# MCU-STM32F767.net
KiCad netlist of a schematic drawn in Altium Designer
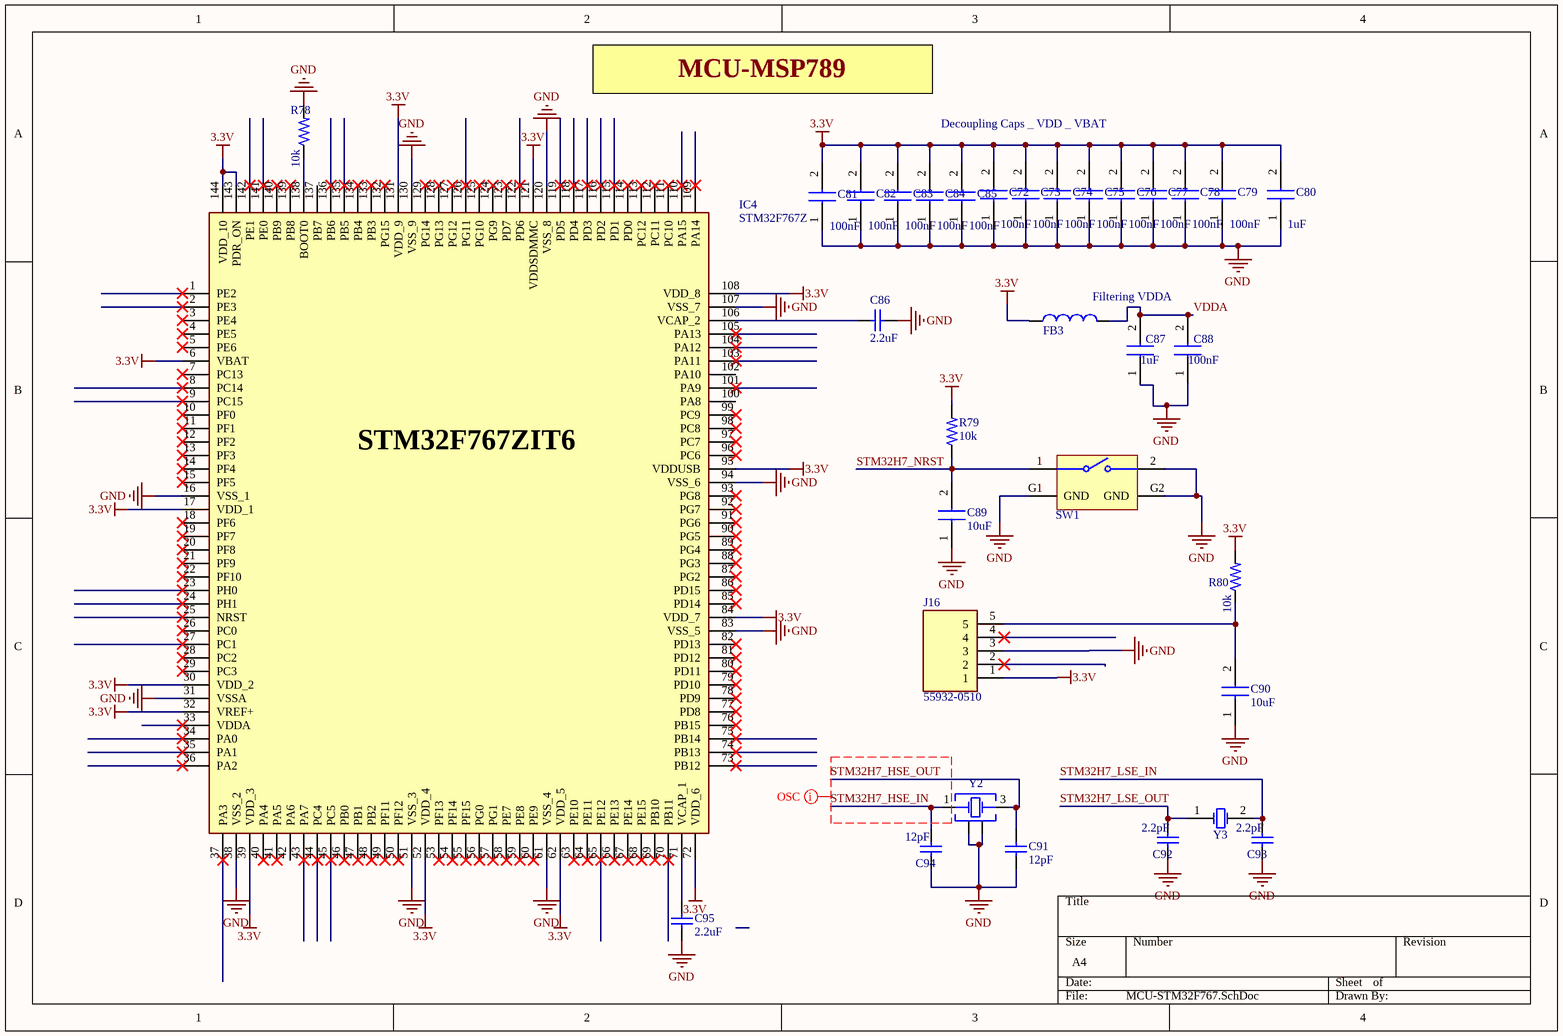
[diagram p0: MCU-STM32F767.SchDoc]

(export (version "E")
  (design (tool "Eeschema 10.0.6"))
  (components
    (comp (ref "C72")
      (value "100nF")
      (footprint "CAPC1005X55N")
      (description "Capacitor")
      (fields
        (field (name "MANUFACTURER_PART_NUMBER") "CL05B104KO5NNNC")
        (field (name "MOUSER PART NUMBER") "187-CL05B104KO5NNNC")
      )
      (libsource (lib "lib-hiony") (part "6V 100nF X7R ±10% 0402 Multilayer"))
    )
    (comp (ref "C73")
      (value "100nF")
      (footprint "CAPC1005X55N")
      (description "Capacitor")
      (fields
        (field (name "MANUFACTURER_PART_NUMBER") "CL05B104KO5NNNC")
        (field (name "MOUSER PART NUMBER") "187-CL05B104KO5NNNC")
      )
      (libsource (lib "lib-hiony") (part "6V 100nF X7R ±10% 0402 Multilayer"))
    )
    (comp (ref "C74")
      (value "100nF")
      (footprint "CAPC1005X55N")
      (description "Capacitor")
      (fields
        (field (name "MANUFACTURER_PART_NUMBER") "CL05B104KO5NNNC")
        (field (name "MOUSER PART NUMBER") "187-CL05B104KO5NNNC")
      )
      (libsource (lib "lib-hiony") (part "6V 100nF X7R ±10% 0402 Multilayer"))
    )
    (comp (ref "C75")
      (value "100nF")
      (footprint "CAPC1005X55N")
      (description "Capacitor")
      (fields
        (field (name "MANUFACTURER_PART_NUMBER") "CL05B104KO5NNNC")
        (field (name "MOUSER PART NUMBER") "187-CL05B104KO5NNNC")
      )
      (libsource (lib "lib-hiony") (part "6V 100nF X7R ±10% 0402 Multilayer"))
    )
    (comp (ref "C76")
      (value "100nF")
      (footprint "CAPC1005X55N")
      (description "Capacitor")
      (fields
        (field (name "MANUFACTURER_PART_NUMBER") "CL05B104KO5NNNC")
        (field (name "MOUSER PART NUMBER") "187-CL05B104KO5NNNC")
      )
      (libsource (lib "lib-hiony") (part "6V 100nF X7R ±10% 0402 Multilayer"))
    )
    (comp (ref "C77")
      (value "100nF")
      (footprint "CAPC1005X55N")
      (description "Capacitor")
      (fields
        (field (name "MANUFACTURER_PART_NUMBER") "CL05B104KO5NNNC")
        (field (name "MOUSER PART NUMBER") "187-CL05B104KO5NNNC")
      )
      (libsource (lib "lib-hiony") (part "6V 100nF X7R ±10% 0402 Multilayer"))
    )
    (comp (ref "C78")
      (value "100nF")
      (footprint "CAPC1005X55N")
      (description "Capacitor")
      (fields
        (field (name "MANUFACTURER_PART_NUMBER") "CL05B104KO5NNNC")
        (field (name "MOUSER PART NUMBER") "187-CL05B104KO5NNNC")
      )
      (libsource (lib "lib-hiony") (part "6V 100nF X7R ±10% 0402 Multilayer"))
    )
    (comp (ref "C79")
      (value "100nF")
      (footprint "CAPC1005X55N")
      (description "Capacitor")
      (fields
        (field (name "MANUFACTURER_PART_NUMBER") "CL05B104KO5NNNC")
        (field (name "MOUSER PART NUMBER") "187-CL05B104KO5NNNC")
      )
      (libsource (lib "lib-hiony") (part "6V 100nF X7R ±10% 0402 Multilayer"))
    )
    (comp (ref "C80")
      (value "1uF")
      (footprint "CAPC1005X55N")
      (description "Capacitor")
      (fields
        (field (name "MANUFACTURER_PART_NUMBER") "CL05B104KO5NNNC")
        (field (name "MOUSER PART NUMBER") "187-CL05B104KO5NNNC")
      )
      (libsource (lib "lib-hiony") (part "6V 100nF X7R ±10% 0402 Multilayer"))
    )
    (comp (ref "C81")
      (value "100nF")
      (footprint "CAPC1005X55N")
      (description "Capacitor")
      (fields
        (field (name "MANUFACTURER_PART_NUMBER") "CL05B104KO5NNNC")
        (field (name "MOUSER PART NUMBER") "187-CL05B104KO5NNNC")
      )
      (libsource (lib "lib-hiony") (part "6V 100nF X7R ±10% 0402 Multilayer"))
    )
    (comp (ref "C82")
      (value "100nF")
      (footprint "CAPC1005X55N")
      (description "Capacitor")
      (fields
        (field (name "MANUFACTURER_PART_NUMBER") "CL05B104KO5NNNC")
        (field (name "MOUSER PART NUMBER") "187-CL05B104KO5NNNC")
      )
      (libsource (lib "lib-hiony") (part "6V 100nF X7R ±10% 0402 Multilayer"))
    )
    (comp (ref "C83")
      (value "100nF")
      (footprint "CAPC1005X55N")
      (description "Capacitor")
      (fields
        (field (name "MANUFACTURER_PART_NUMBER") "CL05B104KO5NNNC")
        (field (name "MOUSER PART NUMBER") "187-CL05B104KO5NNNC")
      )
      (libsource (lib "lib-hiony") (part "6V 100nF X7R ±10% 0402 Multilayer"))
    )
    (comp (ref "C84")
      (value "100nF")
      (footprint "CAPC1005X55N")
      (description "Capacitor")
      (fields
        (field (name "MANUFACTURER_PART_NUMBER") "CL05B104KO5NNNC")
        (field (name "MOUSER PART NUMBER") "187-CL05B104KO5NNNC")
      )
      (libsource (lib "lib-hiony") (part "6V 100nF X7R ±10% 0402 Multilayer"))
    )
    (comp (ref "C85")
      (value "100nF")
      (footprint "CAPC1005X55N")
      (description "Capacitor")
      (fields
        (field (name "MANUFACTURER_PART_NUMBER") "CL05B104KO5NNNC")
        (field (name "MOUSER PART NUMBER") "187-CL05B104KO5NNNC")
      )
      (libsource (lib "lib-hiony") (part "6V 100nF X7R ±10% 0402 Multilayer"))
    )
    (comp (ref "C86")
      (value "2.2uF")
      (footprint "WCAP-CSST_0603_L1.6W0.8H0.8_Reflow")
      (fields
        (field (name "MANUFACTURER PART NUMBER") "885382206001")
        (field (name "MANUFACTURER") "Wurth Elektronik")
      )
      (libsource (lib "Schlib1") (part "0.1uF capacitor"))
    )
    (comp (ref "C87")
      (value "1uF")
      (footprint "CAPC1005X55N")
      (description "Capacitor")
      (fields
        (field (name "MANUFACTURER_PART_NUMBER") "CL05B104KO5NNNC")
        (field (name "MOUSER PART NUMBER") "187-CL05B104KO5NNNC")
      )
      (libsource (lib "*") (part "CL05B104KO5NNNC"))
    )
    (comp (ref "C88")
      (value "100nF")
      (footprint "CAPC1005X55N")
      (description "Capacitor")
      (fields
        (field (name "MANUFACTURER_PART_NUMBER") "CL05B104KO5NNNC")
        (field (name "MOUSER PART NUMBER") "187-CL05B104KO5NNNC")
      )
      (libsource (lib "*") (part "CL05B104KO5NNNC"))
    )
    (comp (ref "C89")
      (value "10uF")
      (footprint "CAPC1005X55N")
      (description "Capacitor")
      (fields
        (field (name "MANUFACTURER_PART_NUMBER") "CC0603KRX7R9BB104")
        (field (name "MOUSER PART NUMBER") "603-CC603KRX7R9BB104")
      )
      (libsource (lib "Schlib1") (part "0.1uF_603_Capacitor_NL"))
    )
    (comp (ref "C90")
      (value "10uF")
      (footprint "CAPC1005X55N")
      (description "Capacitor")
      (fields
        (field (name "MANUFACTURER_PART_NUMBER") "CC0603KRX7R9BB104")
        (field (name "MOUSER PART NUMBER") "603-CC603KRX7R9BB104")
      )
      (libsource (lib "Schlib1") (part "0.1uF_603_Capacitor_NL"))
    )
    (comp (ref "C91")
      (value "12pF")
      (footprint "WCAP-CSST_0603_L1.6W0.8H0.8_Reflow")
      (fields
        (field (name "MANUFACTURER PART NUMBER") "885382206001")
        (field (name "MANUFACTURER") "Wurth Elektronik")
      )
      (libsource (lib "Schlib1") (part "0.1uF capacitor"))
    )
    (comp (ref "C92")
      (value "2.2pF")
      (footprint "WCAP-CSST_0603_L1.6W0.8H0.8_Reflow")
      (fields
        (field (name "MANUFACTURER PART NUMBER") "885382206001")
        (field (name "MANUFACTURER") "Wurth Elektronik")
      )
      (libsource (lib "Schlib1") (part "0.1uF capacitor"))
    )
    (comp (ref "C93")
      (value "2.2pF")
      (footprint "WCAP-CSST_0603_L1.6W0.8H0.8_Reflow")
      (fields
        (field (name "MANUFACTURER PART NUMBER") "885382206001")
        (field (name "MANUFACTURER") "Wurth Elektronik")
      )
      (libsource (lib "Schlib1") (part "0.1uF capacitor"))
    )
    (comp (ref "C94")
      (value "12pF")
      (footprint "WCAP-CSST_0603_L1.6W0.8H0.8_Reflow")
      (fields
        (field (name "MANUFACTURER PART NUMBER") "885382206001")
        (field (name "MANUFACTURER") "Wurth Elektronik")
      )
      (libsource (lib "Schlib1") (part "0.1uF capacitor"))
    )
    (comp (ref "C95")
      (value "2.2uF")
      (footprint "WCAP-CSST_0603_L1.6W0.8H0.8_Reflow")
      (fields
        (field (name "MANUFACTURER PART NUMBER") "885382206001")
        (field (name "MANUFACTURER") "Wurth Elektronik")
      )
      (libsource (lib "Schlib1") (part "0.1uF capacitor"))
    )
    (comp (ref "FB3")
      (value "10Ohm")
      (footprint "WE-CBA_0603_L1.6W0.8H0.8_HF/HS/WB")
      (description "WE-CBA SMT EMI Suppression Ferrite Bead, size 0201, 10Ohm, 0.65A")
      (fields
        (field (name "MANUFACTURER PART NUMBER") "782219100")
        (field (name "MANUFACTURER") "Wurth Elektronik")
      )
      (libsource (lib "Schlib1") (part "Ferrite-Beads_0603"))
    )
    (comp (ref "IC4")
      (value "STM32F767Z")
      (footprint "QFP50P2200X2200X160-144N")
      (description "Integrated Circuit")
      (fields
        (field (name "MANUFACTURER_PART_NUMBER") "STM32F767ZGT6")
        (field (name "MOUSER PART NUMBER") "511-STM32F767ZGT6")
      )
      (libsource (lib "Schlib1") (part "STM32F767Z"))
    )
    (comp (ref "J16")
      (value "55932-0510")
      (footprint "559320510")
      (description "Connector")
      (fields (field (name "MOUSER PART NUMBER") "538-55932-0510"))
      (libsource (lib "Schlib1") (part "SWD_DEBEG"))
    )
    (comp (ref "R78")
      (value "10k")
      (footprint "RESC2012X65N")
      (description "Fixed Resistors")
      (fields (field (name "MP") "CRG0805F33R") (field (name "MF") "TE Connectivity"))
      (libsource (lib "Schlib1") (part "resisitor"))
    )
    (comp (ref "R79")
      (value "10k")
      (footprint "RESC2012X65N")
      (description "Fixed Resistors")
      (fields (field (name "MP") "CRG0805F33R") (field (name "MF") "TE Connectivity"))
      (libsource (lib "Schlib1") (part "resisitor"))
    )
    (comp (ref "R80")
      (value "10k")
      (footprint "RESC2012X65N")
      (description "Fixed Resistors")
      (fields (field (name "MP") "CRG0805F33R") (field (name "MF") "TE Connectivity"))
      (libsource (lib "Schlib1") (part "resisitor"))
    )
    (comp (ref "SW1")
      (value "431256058716")
      (footprint "4312560587x6")
      (description "WS-TATU THT Tact Switch 6x6mm Right Angled Type with ground terminal, SPST-NO, 12VDC, 50mA, 160g")
      (fields (field (name "MANUFACTURER") "Wurth Elektronik"))
      (libsource (lib "Schlib1") (part "reset_button"))
    )
    (comp (ref "Y2")
      (value "25MHz")
      (footprint "WE-XTAL_CFPX-180")
      (description "WE-XTAL Quartz Crystal, SMT, CFPX-180, 25MHz, +/-10ppm")
      (fields
        (field (name "MANUFACTURER PART NUMBER") "830108174209")
        (field (name "MANUFACTURER") "Wurth Elektronik")
      )
      (libsource (lib "Schlib1") (part "Crystals"))
    )
    (comp (ref "Y3")
      (value "32.768kHz")
      (footprint "WE-XTAL_IQXC-25")
      (description "WE-XTAL Watch Crystal, SMT, IQXC-25, 32.768kHz, +/-10ppm")
      (fields
        (field (name "MANUFACTURER PART NUMBER") "830062558")
        (field (name "MANUFACTURER") "Wurth Elektronik")
      )
      (libsource (lib "Schlib1") (part "CRYSTAL 32.768kH"))
    )
  )
  (nets
    (net (code "1") (name "/STM32H7_HSE_IN") (class "Default")
      (node (ref "C94") (pin "1") (pinfunction "1_1") (pintype "passive"))
      (node (ref "Y2") (pin "1") (pinfunction "Crystal_1") (pintype "passive"))
    )
    (net (code "2") (name "/STM32H7_HSE_OUT") (class "Default")
      (node (ref "C91") (pin "1") (pinfunction "1_1") (pintype "passive"))
      (node (ref "Y2") (pin "3") (pinfunction "Crystal_3") (pintype "passive"))
    )
    (net (code "3") (name "/STM32H7_LSE_IN") (class "Default")
      (node (ref "C93") (pin "1") (pinfunction "1_1") (pintype "passive"))
      (node (ref "Y3") (pin "2") (pinfunction "OSC2_2") (pintype "passive"))
    )
    (net (code "4") (name "/STM32H7_LSE_OUT") (class "Default")
      (node (ref "C92") (pin "1") (pinfunction "1_1") (pintype "passive"))
      (node (ref "Y3") (pin "1") (pinfunction "OSC1_1") (pintype "passive"))
    )
    (net (code "5") (name "/STM32H7_NRST") (class "Default")
      (node (ref "C89") (pin "2") (pinfunction "2_2") (pintype "passive"))
      (node (ref "R79") (pin "1") (pinfunction "1_1") (pintype "passive"))
      (node (ref "SW1") (pin "1") (pinfunction "1_1") (pintype "passive"))
    )
    (net (code "6") (name "/VDDA") (class "Default")
      (node (ref "C87") (pin "2") (pinfunction "2_2") (pintype "passive"))
      (node (ref "C88") (pin "2") (pinfunction "2_2") (pintype "passive"))
      (node (ref "FB3") (pin "2") (pinfunction "2_2") (pintype "passive"))
    )
    (net (code "7") (name "3.3V") (class "Default")
      (node (ref "C72") (pin "2") (pinfunction "2_2") (pintype "passive"))
      (node (ref "C73") (pin "2") (pinfunction "2_2") (pintype "passive"))
      (node (ref "C74") (pin "2") (pinfunction "2_2") (pintype "passive"))
      (node (ref "C75") (pin "2") (pinfunction "2_2") (pintype "passive"))
      (node (ref "C76") (pin "2") (pinfunction "2_2") (pintype "passive"))
      (node (ref "C77") (pin "2") (pinfunction "2_2") (pintype "passive"))
      (node (ref "C78") (pin "2") (pinfunction "2_2") (pintype "passive"))
      (node (ref "C79") (pin "2") (pinfunction "2_2") (pintype "passive"))
      (node (ref "C80") (pin "2") (pinfunction "2_2") (pintype "passive"))
      (node (ref "C81") (pin "2") (pinfunction "2_2") (pintype "passive"))
      (node (ref "C82") (pin "2") (pinfunction "2_2") (pintype "passive"))
      (node (ref "C83") (pin "2") (pinfunction "2_2") (pintype "passive"))
      (node (ref "C84") (pin "2") (pinfunction "2_2") (pintype "passive"))
      (node (ref "C85") (pin "2") (pinfunction "2_2") (pintype "passive"))
      (node (ref "FB3") (pin "1") (pinfunction "1_1") (pintype "passive"))
      (node (ref "IC4") (pin "108") (pinfunction "VDD_8_108") (pintype "passive"))
      (node (ref "IC4") (pin "121") (pinfunction "VDDSDMMC_121") (pintype "passive"))
      (node (ref "IC4") (pin "131") (pinfunction "VDD_9_131") (pintype "passive"))
      (node (ref "IC4") (pin "143") (pinfunction "PDR_ON_143") (pintype "passive"))
      (node (ref "IC4") (pin "144") (pinfunction "VDD_10_144") (pintype "passive"))
      (node (ref "IC4") (pin "17") (pinfunction "VDD_1_17") (pintype "passive"))
      (node (ref "IC4") (pin "30") (pinfunction "VDD_2_30") (pintype "passive"))
      (node (ref "IC4") (pin "32") (pinfunction "VREF+_32") (pintype "passive"))
      (node (ref "IC4") (pin "39") (pinfunction "VDD_3_39") (pintype "passive"))
      (node (ref "IC4") (pin "52") (pinfunction "VDD_4_52") (pintype "passive"))
      (node (ref "IC4") (pin "6") (pinfunction "VBAT_6") (pintype "passive"))
      (node (ref "IC4") (pin "62") (pinfunction "VDD_5_62") (pintype "passive"))
      (node (ref "IC4") (pin "72") (pinfunction "VDD_6_72") (pintype "passive"))
      (node (ref "IC4") (pin "84") (pinfunction "VDD_7_84") (pintype "passive"))
      (node (ref "IC4") (pin "95") (pinfunction "VDDUSB_95") (pintype "passive"))
      (node (ref "J16") (pin "1") (pinfunction "1_1") (pintype "passive"))
      (node (ref "R79") (pin "2") (pinfunction "2_2") (pintype "passive"))
      (node (ref "R80") (pin "2") (pinfunction "2_2") (pintype "passive"))
    )
    (net (code "8") (name "GND") (class "Default")
      (node (ref "C72") (pin "1") (pinfunction "1_1") (pintype "passive"))
      (node (ref "C73") (pin "1") (pinfunction "1_1") (pintype "passive"))
      (node (ref "C74") (pin "1") (pinfunction "1_1") (pintype "passive"))
      (node (ref "C75") (pin "1") (pinfunction "1_1") (pintype "passive"))
      (node (ref "C76") (pin "1") (pinfunction "1_1") (pintype "passive"))
      (node (ref "C77") (pin "1") (pinfunction "1_1") (pintype "passive"))
      (node (ref "C78") (pin "1") (pinfunction "1_1") (pintype "passive"))
      (node (ref "C79") (pin "1") (pinfunction "1_1") (pintype "passive"))
      (node (ref "C80") (pin "1") (pinfunction "1_1") (pintype "passive"))
      (node (ref "C81") (pin "1") (pinfunction "1_1") (pintype "passive"))
      (node (ref "C82") (pin "1") (pinfunction "1_1") (pintype "passive"))
      (node (ref "C83") (pin "1") (pinfunction "1_1") (pintype "passive"))
      (node (ref "C84") (pin "1") (pinfunction "1_1") (pintype "passive"))
      (node (ref "C85") (pin "1") (pinfunction "1_1") (pintype "passive"))
      (node (ref "C86") (pin "2") (pinfunction "2_2") (pintype "passive"))
      (node (ref "C87") (pin "1") (pinfunction "1_1") (pintype "passive"))
      (node (ref "C88") (pin "1") (pinfunction "1_1") (pintype "passive"))
      (node (ref "C89") (pin "1") (pinfunction "1_1") (pintype "passive"))
      (node (ref "C90") (pin "1") (pinfunction "1_1") (pintype "passive"))
      (node (ref "C91") (pin "2") (pinfunction "2_2") (pintype "passive"))
      (node (ref "C92") (pin "2") (pinfunction "2_2") (pintype "passive"))
      (node (ref "C93") (pin "2") (pinfunction "2_2") (pintype "passive"))
      (node (ref "C94") (pin "2") (pinfunction "2_2") (pintype "passive"))
      (node (ref "C95") (pin "1") (pinfunction "1_1") (pintype "passive"))
      (node (ref "IC4") (pin "107") (pinfunction "VSS_7_107") (pintype "passive"))
      (node (ref "IC4") (pin "120") (pinfunction "VSS_8_120") (pintype "passive"))
      (node (ref "IC4") (pin "130") (pinfunction "VSS_9_130") (pintype "passive"))
      (node (ref "IC4") (pin "16") (pinfunction "VSS_1_16") (pintype "passive"))
      (node (ref "IC4") (pin "31") (pinfunction "VSSA_31") (pintype "passive"))
      (node (ref "IC4") (pin "38") (pinfunction "VSS_2_38") (pintype "passive"))
      (node (ref "IC4") (pin "51") (pinfunction "VSS_3_51") (pintype "passive"))
      (node (ref "IC4") (pin "61") (pinfunction "VSS_4_61") (pintype "passive"))
      (node (ref "IC4") (pin "83") (pinfunction "VSS_5_83") (pintype "passive"))
      (node (ref "IC4") (pin "94") (pinfunction "VSS_6_94") (pintype "passive"))
      (node (ref "J16") (pin "3") (pinfunction "3_3") (pintype "passive"))
      (node (ref "R78") (pin "2") (pinfunction "2_2") (pintype "passive"))
      (node (ref "SW1") (pin "2") (pinfunction "2_2") (pintype "passive"))
      (node (ref "SW1") (pin "G1") (pinfunction "GND_G1") (pintype "passive"))
      (node (ref "SW1") (pin "G2") (pinfunction "GND_G2") (pintype "passive"))
      (node (ref "Y2") (pin "2") (pinfunction "GND&Lid_2") (pintype "passive"))
      (node (ref "Y2") (pin "4") (pinfunction "GND&Lid_4") (pintype "passive"))
    )
    (net (code "9") (name "Net-(C90-Pad2)") (class "Default")
      (node (ref "C90") (pin "2") (pinfunction "2_2") (pintype "passive"))
      (node (ref "J16") (pin "5") (pinfunction "5_5") (pintype "passive"))
      (node (ref "R80") (pin "1") (pinfunction "1_1") (pintype "passive"))
    )
    (net (code "10") (name "Net-(IC4-BOOT0)") (class "Default")
      (node (ref "IC4") (pin "138") (pinfunction "BOOT0_138") (pintype "passive"))
      (node (ref "R78") (pin "1") (pinfunction "1_1") (pintype "passive"))
    )
    (net (code "11") (name "Net-(IC4-VCAP_1)") (class "Default")
      (node (ref "C95") (pin "2") (pinfunction "2_2") (pintype "passive"))
      (node (ref "IC4") (pin "71") (pinfunction "VCAP_1_71") (pintype "passive"))
    )
    (net (code "12") (name "Net-(IC4-VCAP_2)") (class "Default")
      (node (ref "C86") (pin "1") (pinfunction "1_1") (pintype "passive"))
      (node (ref "IC4") (pin "106") (pinfunction "VCAP_2_106") (pintype "passive"))
    )
    (net (code "13") (name "unconnected-(IC4-NRST-Pad25)") (class "Default")
      (node (ref "IC4") (pin "25") (pinfunction "NRST_25") (pintype "passive+no_connect"))
    )
    (net (code "14") (name "unconnected-(IC4-PA0-Pad34)") (class "Default")
      (node (ref "IC4") (pin "34") (pinfunction "PA0_34") (pintype "passive+no_connect"))
    )
    (net (code "15") (name "unconnected-(IC4-PA1-Pad35)") (class "Default")
      (node (ref "IC4") (pin "35") (pinfunction "PA1_35") (pintype "passive+no_connect"))
    )
    (net (code "16") (name "unconnected-(IC4-PA2-Pad36)") (class "Default")
      (node (ref "IC4") (pin "36") (pinfunction "PA2_36") (pintype "passive+no_connect"))
    )
    (net (code "17") (name "unconnected-(IC4-PA3-Pad37)") (class "Default")
      (node (ref "IC4") (pin "37") (pinfunction "PA3_37") (pintype "passive+no_connect"))
    )
    (net (code "18") (name "unconnected-(IC4-PA4-Pad40)") (class "Default")
      (node (ref "IC4") (pin "40") (pinfunction "PA4_40") (pintype "passive+no_connect"))
    )
    (net (code "19") (name "unconnected-(IC4-PA5-Pad41)") (class "Default")
      (node (ref "IC4") (pin "41") (pinfunction "PA5_41") (pintype "passive+no_connect"))
    )
    (net (code "20") (name "unconnected-(IC4-PA6-Pad42)") (class "Default")
      (node (ref "IC4") (pin "42") (pinfunction "PA6_42") (pintype "passive"))
    )
    (net (code "21") (name "unconnected-(IC4-PA7-Pad43)") (class "Default")
      (node (ref "IC4") (pin "43") (pinfunction "PA7_43") (pintype "passive+no_connect"))
    )
    (net (code "22") (name "unconnected-(IC4-PA8-Pad100)") (class "Default")
      (node (ref "IC4") (pin "100") (pinfunction "PA8_100") (pintype "passive"))
    )
    (net (code "23") (name "unconnected-(IC4-PA9-Pad101)") (class "Default")
      (node (ref "IC4") (pin "101") (pinfunction "PA9_101") (pintype "passive+no_connect"))
    )
    (net (code "24") (name "unconnected-(IC4-PA10-Pad102)") (class "Default")
      (node (ref "IC4") (pin "102") (pinfunction "PA10_102") (pintype "passive"))
    )
    (net (code "25") (name "unconnected-(IC4-PA11-Pad103)") (class "Default")
      (node (ref "IC4") (pin "103") (pinfunction "PA11_103") (pintype "passive+no_connect"))
    )
    (net (code "26") (name "unconnected-(IC4-PA12-Pad104)") (class "Default")
      (node (ref "IC4") (pin "104") (pinfunction "PA12_104") (pintype "passive+no_connect"))
    )
    (net (code "27") (name "unconnected-(IC4-PA13-Pad105)") (class "Default")
      (node (ref "IC4") (pin "105") (pinfunction "PA13_105") (pintype "passive+no_connect"))
    )
    (net (code "28") (name "unconnected-(IC4-PA14-Pad109)") (class "Default")
      (node (ref "IC4") (pin "109") (pinfunction "PA14_109") (pintype "passive+no_connect"))
    )
    (net (code "29") (name "unconnected-(IC4-PA15-Pad110)") (class "Default")
      (node (ref "IC4") (pin "110") (pinfunction "PA15_110") (pintype "passive+no_connect"))
    )
    (net (code "30") (name "unconnected-(IC4-PB0-Pad46)") (class "Default")
      (node (ref "IC4") (pin "46") (pinfunction "PB0_46") (pintype "passive+no_connect"))
    )
    (net (code "31") (name "unconnected-(IC4-PB1-Pad47)") (class "Default")
      (node (ref "IC4") (pin "47") (pinfunction "PB1_47") (pintype "passive+no_connect"))
    )
    (net (code "32") (name "unconnected-(IC4-PB2-Pad48)") (class "Default")
      (node (ref "IC4") (pin "48") (pinfunction "PB2_48") (pintype "passive+no_connect"))
    )
    (net (code "33") (name "unconnected-(IC4-PB3-Pad133)") (class "Default")
      (node (ref "IC4") (pin "133") (pinfunction "PB3_133") (pintype "passive+no_connect"))
    )
    (net (code "34") (name "unconnected-(IC4-PB4-Pad134)") (class "Default")
      (node (ref "IC4") (pin "134") (pinfunction "PB4_134") (pintype "passive+no_connect"))
    )
    (net (code "35") (name "unconnected-(IC4-PB5-Pad135)") (class "Default")
      (node (ref "IC4") (pin "135") (pinfunction "PB5_135") (pintype "passive+no_connect"))
    )
    (net (code "36") (name "unconnected-(IC4-PB6-Pad136)") (class "Default")
      (node (ref "IC4") (pin "136") (pinfunction "PB6_136") (pintype "passive+no_connect"))
    )
    (net (code "37") (name "unconnected-(IC4-PB7-Pad137)") (class "Default")
      (node (ref "IC4") (pin "137") (pinfunction "PB7_137") (pintype "passive"))
    )
    (net (code "38") (name "unconnected-(IC4-PB8-Pad139)") (class "Default")
      (node (ref "IC4") (pin "139") (pinfunction "PB8_139") (pintype "passive+no_connect"))
    )
    (net (code "39") (name "unconnected-(IC4-PB9-Pad140)") (class "Default")
      (node (ref "IC4") (pin "140") (pinfunction "PB9_140") (pintype "passive+no_connect"))
    )
    (net (code "40") (name "unconnected-(IC4-PB10-Pad69)") (class "Default")
      (node (ref "IC4") (pin "69") (pinfunction "PB10_69") (pintype "passive+no_connect"))
    )
    (net (code "41") (name "unconnected-(IC4-PB11-Pad70)") (class "Default")
      (node (ref "IC4") (pin "70") (pinfunction "PB11_70") (pintype "passive+no_connect"))
    )
    (net (code "42") (name "unconnected-(IC4-PB12-Pad73)") (class "Default")
      (node (ref "IC4") (pin "73") (pinfunction "PB12_73") (pintype "passive+no_connect"))
    )
    (net (code "43") (name "unconnected-(IC4-PB13-Pad74)") (class "Default")
      (node (ref "IC4") (pin "74") (pinfunction "PB13_74") (pintype "passive+no_connect"))
    )
    (net (code "44") (name "unconnected-(IC4-PB14-Pad75)") (class "Default")
      (node (ref "IC4") (pin "75") (pinfunction "PB14_75") (pintype "passive+no_connect"))
    )
    (net (code "45") (name "unconnected-(IC4-PB15-Pad76)") (class "Default")
      (node (ref "IC4") (pin "76") (pinfunction "PB15_76") (pintype "passive+no_connect"))
    )
    (net (code "46") (name "unconnected-(IC4-PC0-Pad26)") (class "Default")
      (node (ref "IC4") (pin "26") (pinfunction "PC0_26") (pintype "passive+no_connect"))
    )
    (net (code "47") (name "unconnected-(IC4-PC1-Pad27)") (class "Default")
      (node (ref "IC4") (pin "27") (pinfunction "PC1_27") (pintype "passive+no_connect"))
    )
    (net (code "48") (name "unconnected-(IC4-PC2-Pad28)") (class "Default")
      (node (ref "IC4") (pin "28") (pinfunction "PC2_28") (pintype "passive+no_connect"))
    )
    (net (code "49") (name "unconnected-(IC4-PC3-Pad29)") (class "Default")
      (node (ref "IC4") (pin "29") (pinfunction "PC3_29") (pintype "passive+no_connect"))
    )
    (net (code "50") (name "unconnected-(IC4-PC4-Pad44)") (class "Default")
      (node (ref "IC4") (pin "44") (pinfunction "PC4_44") (pintype "passive+no_connect"))
    )
    (net (code "51") (name "unconnected-(IC4-PC5-Pad45)") (class "Default")
      (node (ref "IC4") (pin "45") (pinfunction "PC5_45") (pintype "passive+no_connect"))
    )
    (net (code "52") (name "unconnected-(IC4-PC6-Pad96)") (class "Default")
      (node (ref "IC4") (pin "96") (pinfunction "PC6_96") (pintype "passive+no_connect"))
    )
    (net (code "53") (name "unconnected-(IC4-PC7-Pad97)") (class "Default")
      (node (ref "IC4") (pin "97") (pinfunction "PC7_97") (pintype "passive+no_connect"))
    )
    (net (code "54") (name "unconnected-(IC4-PC8-Pad98)") (class "Default")
      (node (ref "IC4") (pin "98") (pinfunction "PC8_98") (pintype "passive+no_connect"))
    )
    (net (code "55") (name "unconnected-(IC4-PC9-Pad99)") (class "Default")
      (node (ref "IC4") (pin "99") (pinfunction "PC9_99") (pintype "passive+no_connect"))
    )
    (net (code "56") (name "unconnected-(IC4-PC10-Pad111)") (class "Default")
      (node (ref "IC4") (pin "111") (pinfunction "PC10_111") (pintype "passive+no_connect"))
    )
    (net (code "57") (name "unconnected-(IC4-PC11-Pad112)") (class "Default")
      (node (ref "IC4") (pin "112") (pinfunction "PC11_112") (pintype "passive+no_connect"))
    )
    (net (code "58") (name "unconnected-(IC4-PC12-Pad113)") (class "Default")
      (node (ref "IC4") (pin "113") (pinfunction "PC12_113") (pintype "passive+no_connect"))
    )
    (net (code "59") (name "unconnected-(IC4-PC13-Pad7)") (class "Default")
      (node (ref "IC4") (pin "7") (pinfunction "PC13_7") (pintype "passive+no_connect"))
    )
    (net (code "60") (name "unconnected-(IC4-PC14-Pad8)") (class "Default")
      (node (ref "IC4") (pin "8") (pinfunction "PC14_8") (pintype "passive+no_connect"))
    )
    (net (code "61") (name "unconnected-(IC4-PC15-Pad9)") (class "Default")
      (node (ref "IC4") (pin "9") (pinfunction "PC15_9") (pintype "passive+no_connect"))
    )
    (net (code "62") (name "unconnected-(IC4-PD0-Pad114)") (class "Default")
      (node (ref "IC4") (pin "114") (pinfunction "PD0_114") (pintype "passive+no_connect"))
    )
    (net (code "63") (name "unconnected-(IC4-PD1-Pad115)") (class "Default")
      (node (ref "IC4") (pin "115") (pinfunction "PD1_115") (pintype "passive+no_connect"))
    )
    (net (code "64") (name "unconnected-(IC4-PD2-Pad116)") (class "Default")
      (node (ref "IC4") (pin "116") (pinfunction "PD2_116") (pintype "passive+no_connect"))
    )
    (net (code "65") (name "unconnected-(IC4-PD3-Pad117)") (class "Default")
      (node (ref "IC4") (pin "117") (pinfunction "PD3_117") (pintype "passive+no_connect"))
    )
    (net (code "66") (name "unconnected-(IC4-PD4-Pad118)") (class "Default")
      (node (ref "IC4") (pin "118") (pinfunction "PD4_118") (pintype "passive+no_connect"))
    )
    (net (code "67") (name "unconnected-(IC4-PD5-Pad119)") (class "Default")
      (node (ref "IC4") (pin "119") (pinfunction "PD5_119") (pintype "passive+no_connect"))
    )
    (net (code "68") (name "unconnected-(IC4-PD6-Pad122)") (class "Default")
      (node (ref "IC4") (pin "122") (pinfunction "PD6_122") (pintype "passive+no_connect"))
    )
    (net (code "69") (name "unconnected-(IC4-PD7-Pad123)") (class "Default")
      (node (ref "IC4") (pin "123") (pinfunction "PD7_123") (pintype "passive+no_connect"))
    )
    (net (code "70") (name "unconnected-(IC4-PD8-Pad77)") (class "Default")
      (node (ref "IC4") (pin "77") (pinfunction "PD8_77") (pintype "passive+no_connect"))
    )
    (net (code "71") (name "unconnected-(IC4-PD9-Pad78)") (class "Default")
      (node (ref "IC4") (pin "78") (pinfunction "PD9_78") (pintype "passive+no_connect"))
    )
    (net (code "72") (name "unconnected-(IC4-PD10-Pad79)") (class "Default")
      (node (ref "IC4") (pin "79") (pinfunction "PD10_79") (pintype "passive+no_connect"))
    )
    (net (code "73") (name "unconnected-(IC4-PD11-Pad80)") (class "Default")
      (node (ref "IC4") (pin "80") (pinfunction "PD11_80") (pintype "passive+no_connect"))
    )
    (net (code "74") (name "unconnected-(IC4-PD12-Pad81)") (class "Default")
      (node (ref "IC4") (pin "81") (pinfunction "PD12_81") (pintype "passive+no_connect"))
    )
    (net (code "75") (name "unconnected-(IC4-PD13-Pad82)") (class "Default")
      (node (ref "IC4") (pin "82") (pinfunction "PD13_82") (pintype "passive+no_connect"))
    )
    (net (code "76") (name "unconnected-(IC4-PD14-Pad85)") (class "Default")
      (node (ref "IC4") (pin "85") (pinfunction "PD14_85") (pintype "passive+no_connect"))
    )
    (net (code "77") (name "unconnected-(IC4-PD15-Pad86)") (class "Default")
      (node (ref "IC4") (pin "86") (pinfunction "PD15_86") (pintype "passive+no_connect"))
    )
    (net (code "78") (name "unconnected-(IC4-PE0-Pad141)") (class "Default")
      (node (ref "IC4") (pin "141") (pinfunction "PE0_141") (pintype "passive+no_connect"))
    )
    (net (code "79") (name "unconnected-(IC4-PE1-Pad142)") (class "Default")
      (node (ref "IC4") (pin "142") (pinfunction "PE1_142") (pintype "passive+no_connect"))
    )
    (net (code "80") (name "unconnected-(IC4-PE2-Pad1)") (class "Default")
      (node (ref "IC4") (pin "1") (pinfunction "PE2_1") (pintype "passive+no_connect"))
    )
    (net (code "81") (name "unconnected-(IC4-PE3-Pad2)") (class "Default")
      (node (ref "IC4") (pin "2") (pinfunction "PE3_2") (pintype "passive+no_connect"))
    )
    (net (code "82") (name "unconnected-(IC4-PE4-Pad3)") (class "Default")
      (node (ref "IC4") (pin "3") (pinfunction "PE4_3") (pintype "passive+no_connect"))
    )
    (net (code "83") (name "unconnected-(IC4-PE5-Pad4)") (class "Default")
      (node (ref "IC4") (pin "4") (pinfunction "PE5_4") (pintype "passive+no_connect"))
    )
    (net (code "84") (name "unconnected-(IC4-PE6-Pad5)") (class "Default")
      (node (ref "IC4") (pin "5") (pinfunction "PE6_5") (pintype "passive+no_connect"))
    )
    (net (code "85") (name "unconnected-(IC4-PE7-Pad58)") (class "Default")
      (node (ref "IC4") (pin "58") (pinfunction "PE7_58") (pintype "passive+no_connect"))
    )
    (net (code "86") (name "unconnected-(IC4-PE8-Pad59)") (class "Default")
      (node (ref "IC4") (pin "59") (pinfunction "PE8_59") (pintype "passive+no_connect"))
    )
    (net (code "87") (name "unconnected-(IC4-PE9-Pad60)") (class "Default")
      (node (ref "IC4") (pin "60") (pinfunction "PE9_60") (pintype "passive+no_connect"))
    )
    (net (code "88") (name "unconnected-(IC4-PE10-Pad63)") (class "Default")
      (node (ref "IC4") (pin "63") (pinfunction "PE10_63") (pintype "passive+no_connect"))
    )
    (net (code "89") (name "unconnected-(IC4-PE11-Pad64)") (class "Default")
      (node (ref "IC4") (pin "64") (pinfunction "PE11_64") (pintype "passive+no_connect"))
    )
    (net (code "90") (name "unconnected-(IC4-PE12-Pad65)") (class "Default")
      (node (ref "IC4") (pin "65") (pinfunction "PE12_65") (pintype "passive+no_connect"))
    )
    (net (code "91") (name "unconnected-(IC4-PE13-Pad66)") (class "Default")
      (node (ref "IC4") (pin "66") (pinfunction "PE13_66") (pintype "passive+no_connect"))
    )
    (net (code "92") (name "unconnected-(IC4-PE14-Pad67)") (class "Default")
      (node (ref "IC4") (pin "67") (pinfunction "PE14_67") (pintype "passive+no_connect"))
    )
    (net (code "93") (name "unconnected-(IC4-PE15-Pad68)") (class "Default")
      (node (ref "IC4") (pin "68") (pinfunction "PE15_68") (pintype "passive+no_connect"))
    )
    (net (code "94") (name "unconnected-(IC4-PF0-Pad10)") (class "Default")
      (node (ref "IC4") (pin "10") (pinfunction "PF0_10") (pintype "passive+no_connect"))
    )
    (net (code "95") (name "unconnected-(IC4-PF1-Pad11)") (class "Default")
      (node (ref "IC4") (pin "11") (pinfunction "PF1_11") (pintype "passive+no_connect"))
    )
    (net (code "96") (name "unconnected-(IC4-PF2-Pad12)") (class "Default")
      (node (ref "IC4") (pin "12") (pinfunction "PF2_12") (pintype "passive+no_connect"))
    )
    (net (code "97") (name "unconnected-(IC4-PF3-Pad13)") (class "Default")
      (node (ref "IC4") (pin "13") (pinfunction "PF3_13") (pintype "passive+no_connect"))
    )
    (net (code "98") (name "unconnected-(IC4-PF4-Pad14)") (class "Default")
      (node (ref "IC4") (pin "14") (pinfunction "PF4_14") (pintype "passive+no_connect"))
    )
    (net (code "99") (name "unconnected-(IC4-PF5-Pad15)") (class "Default")
      (node (ref "IC4") (pin "15") (pinfunction "PF5_15") (pintype "passive+no_connect"))
    )
    (net (code "100") (name "unconnected-(IC4-PF6-Pad18)") (class "Default")
      (node (ref "IC4") (pin "18") (pinfunction "PF6_18") (pintype "passive+no_connect"))
    )
    (net (code "101") (name "unconnected-(IC4-PF7-Pad19)") (class "Default")
      (node (ref "IC4") (pin "19") (pinfunction "PF7_19") (pintype "passive+no_connect"))
    )
    (net (code "102") (name "unconnected-(IC4-PF8-Pad20)") (class "Default")
      (node (ref "IC4") (pin "20") (pinfunction "PF8_20") (pintype "passive+no_connect"))
    )
    (net (code "103") (name "unconnected-(IC4-PF9-Pad21)") (class "Default")
      (node (ref "IC4") (pin "21") (pinfunction "PF9_21") (pintype "passive+no_connect"))
    )
    (net (code "104") (name "unconnected-(IC4-PF10-Pad22)") (class "Default")
      (node (ref "IC4") (pin "22") (pinfunction "PF10_22") (pintype "passive+no_connect"))
    )
    (net (code "105") (name "unconnected-(IC4-PF11-Pad49)") (class "Default")
      (node (ref "IC4") (pin "49") (pinfunction "PF11_49") (pintype "passive+no_connect"))
    )
    (net (code "106") (name "unconnected-(IC4-PF12-Pad50)") (class "Default")
      (node (ref "IC4") (pin "50") (pinfunction "PF12_50") (pintype "passive+no_connect"))
    )
    (net (code "107") (name "unconnected-(IC4-PF13-Pad53)") (class "Default")
      (node (ref "IC4") (pin "53") (pinfunction "PF13_53") (pintype "passive+no_connect"))
    )
    (net (code "108") (name "unconnected-(IC4-PF14-Pad54)") (class "Default")
      (node (ref "IC4") (pin "54") (pinfunction "PF14_54") (pintype "passive+no_connect"))
    )
    (net (code "109") (name "unconnected-(IC4-PF15-Pad55)") (class "Default")
      (node (ref "IC4") (pin "55") (pinfunction "PF15_55") (pintype "passive+no_connect"))
    )
    (net (code "110") (name "unconnected-(IC4-PG0-Pad56)") (class "Default")
      (node (ref "IC4") (pin "56") (pinfunction "PG0_56") (pintype "passive+no_connect"))
    )
    (net (code "111") (name "unconnected-(IC4-PG1-Pad57)") (class "Default")
      (node (ref "IC4") (pin "57") (pinfunction "PG1_57") (pintype "passive+no_connect"))
    )
    (net (code "112") (name "unconnected-(IC4-PG2-Pad87)") (class "Default")
      (node (ref "IC4") (pin "87") (pinfunction "PG2_87") (pintype "passive+no_connect"))
    )
    (net (code "113") (name "unconnected-(IC4-PG3-Pad88)") (class "Default")
      (node (ref "IC4") (pin "88") (pinfunction "PG3_88") (pintype "passive+no_connect"))
    )
    (net (code "114") (name "unconnected-(IC4-PG4-Pad89)") (class "Default")
      (node (ref "IC4") (pin "89") (pinfunction "PG4_89") (pintype "passive+no_connect"))
    )
    (net (code "115") (name "unconnected-(IC4-PG5-Pad90)") (class "Default")
      (node (ref "IC4") (pin "90") (pinfunction "PG5_90") (pintype "passive+no_connect"))
    )
    (net (code "116") (name "unconnected-(IC4-PG6-Pad91)") (class "Default")
      (node (ref "IC4") (pin "91") (pinfunction "PG6_91") (pintype "passive+no_connect"))
    )
    (net (code "117") (name "unconnected-(IC4-PG7-Pad92)") (class "Default")
      (node (ref "IC4") (pin "92") (pinfunction "PG7_92") (pintype "passive+no_connect"))
    )
    (net (code "118") (name "unconnected-(IC4-PG8-Pad93)") (class "Default")
      (node (ref "IC4") (pin "93") (pinfunction "PG8_93") (pintype "passive+no_connect"))
    )
    (net (code "119") (name "unconnected-(IC4-PG9-Pad124)") (class "Default")
      (node (ref "IC4") (pin "124") (pinfunction "PG9_124") (pintype "passive+no_connect"))
    )
    (net (code "120") (name "unconnected-(IC4-PG10-Pad125)") (class "Default")
      (node (ref "IC4") (pin "125") (pinfunction "PG10_125") (pintype "passive+no_connect"))
    )
    (net (code "121") (name "unconnected-(IC4-PG11-Pad126)") (class "Default")
      (node (ref "IC4") (pin "126") (pinfunction "PG11_126") (pintype "passive+no_connect"))
    )
    (net (code "122") (name "unconnected-(IC4-PG12-Pad127)") (class "Default")
      (node (ref "IC4") (pin "127") (pinfunction "PG12_127") (pintype "passive+no_connect"))
    )
    (net (code "123") (name "unconnected-(IC4-PG13-Pad128)") (class "Default")
      (node (ref "IC4") (pin "128") (pinfunction "PG13_128") (pintype "passive+no_connect"))
    )
    (net (code "124") (name "unconnected-(IC4-PG14-Pad129)") (class "Default")
      (node (ref "IC4") (pin "129") (pinfunction "PG14_129") (pintype "passive+no_connect"))
    )
    (net (code "125") (name "unconnected-(IC4-PG15-Pad132)") (class "Default")
      (node (ref "IC4") (pin "132") (pinfunction "PG15_132") (pintype "passive+no_connect"))
    )
    (net (code "126") (name "unconnected-(IC4-PH0-Pad23)") (class "Default")
      (node (ref "IC4") (pin "23") (pinfunction "PH0_23") (pintype "passive+no_connect"))
    )
    (net (code "127") (name "unconnected-(IC4-PH1-Pad24)") (class "Default")
      (node (ref "IC4") (pin "24") (pinfunction "PH1_24") (pintype "passive+no_connect"))
    )
    (net (code "128") (name "unconnected-(IC4-VDDA-Pad33)") (class "Default")
      (node (ref "IC4") (pin "33") (pinfunction "VDDA_33") (pintype "passive+no_connect"))
    )
    (net (code "129") (name "unconnected-(J16-Pad2)") (class "Default")
      (node (ref "J16") (pin "2") (pinfunction "2_2") (pintype "passive+no_connect"))
    )
    (net (code "130") (name "unconnected-(J16-Pad4)") (class "Default")
      (node (ref "J16") (pin "4") (pinfunction "4_4") (pintype "passive+no_connect"))
    )
  )
)
